# BNC_IO.net
KiCad netlist of a schematic drawn in Altium Designer
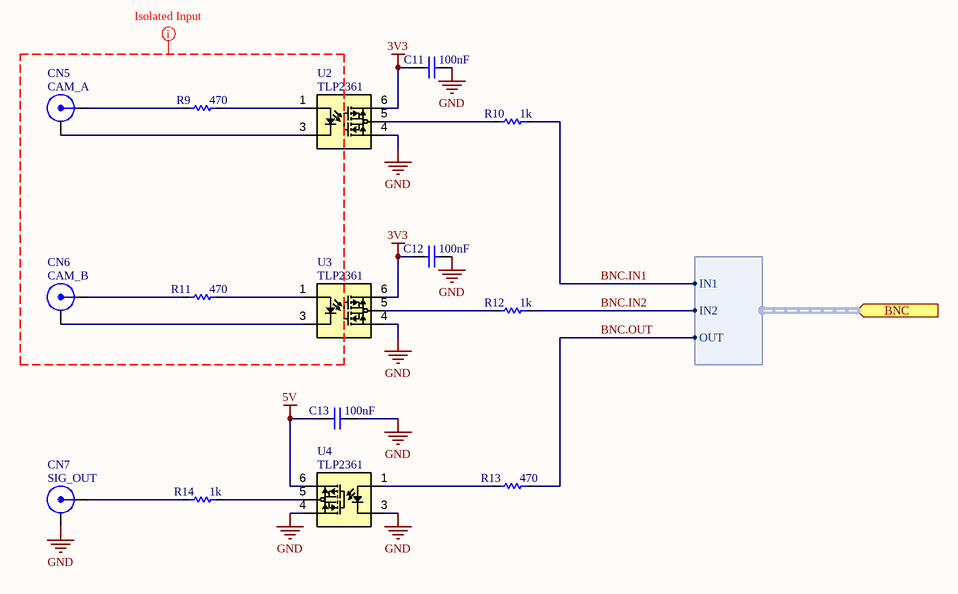
[diagram p0: BNC IO.SchDoc]

(export (version "E")
  (design (tool "Eeschema 10.0.6"))
  (components
    (comp (ref "C11")
      (value "100nF")
      (footprint "CAP_CHIP_0603")
      (description "0603 Multilayer Ceramic Capacitors MLCC")
      (fields (field (name "TOLERANCE") "10%") (field (name "PARTNUMBER") "CC0603KRX7R9BB104"))
      (libsource (lib "Sainsbury Wellcome Centre") (part "Cap"))
    )
    (comp (ref "C12")
      (value "100nF")
      (footprint "CAP_CHIP_0603")
      (description "0603 Multilayer Ceramic Capacitors MLCC")
      (fields (field (name "TOLERANCE") "10%") (field (name "PARTNUMBER") "CC0603KRX7R9BB104"))
      (libsource (lib "Sainsbury Wellcome Centre") (part "Cap"))
    )
    (comp (ref "C13")
      (value "100nF")
      (footprint "CAP_CHIP_0603")
      (description "0603 Multilayer Ceramic Capacitors MLCC")
      (fields (field (name "TOLERANCE") "10%") (field (name "PARTNUMBER") "CC0603KRX7R9BB104"))
      (libsource (lib "Sainsbury Wellcome Centre") (part "Cap"))
    )
    (comp (ref "CN5")
      (value "CAM_A")
      (footprint "BNC-MOLEX-731000105")
      (description "50 Ohms, BNC Right-Angle PCB Jack Receptacle, Nickel Plated Zinc Alloy Body, Low Profile")
      (fields (field (name "PARTNUMBER") "731000105"))
      (libsource (lib "Sainsbury Wellcome Centre") (part "RF-Jack"))
    )
    (comp (ref "CN6")
      (value "CAM_B")
      (footprint "BNC-MOLEX-731000105")
      (description "50 Ohms, BNC Right-Angle PCB Jack Receptacle, Nickel Plated Zinc Alloy Body, Low Profile")
      (fields (field (name "PARTNUMBER") "731000105"))
      (libsource (lib "Sainsbury Wellcome Centre") (part "RF-Jack"))
    )
    (comp (ref "CN7")
      (value "SIG_OUT")
      (footprint "BNC-MOLEX-731000105")
      (description "50 Ohms, BNC Right-Angle PCB Jack Receptacle, Nickel Plated Zinc Alloy Body, Low Profile")
      (fields (field (name "PARTNUMBER") "731000105"))
      (libsource (lib "Sainsbury Wellcome Centre") (part "RF-Jack"))
    )
    (comp (ref "R9")
      (value "470")
      (footprint "RES_CHIP_0603")
      (description "100mW Thick Film Resistors 75V ±100ppm/℃ ±1% 0603 Chip Resistor")
      (fields (field (name "PARTNUMBER") "0603WAF4700T5E") (field (name "TOLERANCE") "1%"))
      (libsource (lib "Sainsbury Wellcome Centre") (part "Res"))
    )
    (comp (ref "R10")
      (value "1k")
      (footprint "RES_CHIP_0603")
      (description "100mW Thick Film Resistors 75V ±100ppm/℃ ±1% 0603 Chip Resistor")
      (fields (field (name "PARTNUMBER") "0603WAF1001T5E") (field (name "TOLERANCE") "1%"))
      (libsource (lib "Sainsbury Wellcome Centre") (part "Res"))
    )
    (comp (ref "R11")
      (value "470")
      (footprint "RES_CHIP_0603")
      (description "100mW Thick Film Resistors 75V ±100ppm/℃ ±1% 0603 Chip Resistor")
      (fields (field (name "PARTNUMBER") "0603WAF4700T5E") (field (name "TOLERANCE") "1%"))
      (libsource (lib "Sainsbury Wellcome Centre") (part "Res"))
    )
    (comp (ref "R12")
      (value "1k")
      (footprint "RES_CHIP_0603")
      (description "100mW Thick Film Resistors 75V ±100ppm/℃ ±1% 0603 Chip Resistor")
      (fields (field (name "PARTNUMBER") "0603WAF1001T5E") (field (name "TOLERANCE") "1%"))
      (libsource (lib "Sainsbury Wellcome Centre") (part "Res"))
    )
    (comp (ref "R13")
      (value "470")
      (footprint "RES_CHIP_0603")
      (description "100mW Thick Film Resistors 75V ±100ppm/℃ ±1% 0603 Chip Resistor")
      (fields (field (name "PARTNUMBER") "0603WAF4700T5E") (field (name "TOLERANCE") "1%"))
      (libsource (lib "Sainsbury Wellcome Centre") (part "Res"))
    )
    (comp (ref "R14")
      (value "1k")
      (footprint "RES_CHIP_0603")
      (description "100mW Thick Film Resistors 75V ±100ppm/℃ ±1% 0603 Chip Resistor")
      (fields (field (name "PARTNUMBER") "0603WAF1001T5E") (field (name "TOLERANCE") "1%"))
      (libsource (lib "Sainsbury Wellcome Centre") (part "Res"))
    )
    (comp (ref "U2")
      (value "TLP2361")
      (footprint "SO5")
      (description "Logic IC Output Optocoupler, 1-Channel, 1-Element, 3750V Isolation, 20MBps")
      (fields (field (name "PARTNUMBER") "TLP2361(TPL,E(T"))
      (libsource (lib "Sainsbury Wellcome Centre") (part "Logic Output Optoisolator"))
    )
    (comp (ref "U3")
      (value "TLP2361")
      (footprint "SO5")
      (description "Logic IC Output Optocoupler, 1-Channel, 1-Element, 3750V Isolation, 20MBps")
      (fields (field (name "PARTNUMBER") "TLP2361(TPL,E(T"))
      (libsource (lib "Sainsbury Wellcome Centre") (part "Logic Output Optoisolator"))
    )
    (comp (ref "U4")
      (value "TLP2361")
      (footprint "SO5")
      (description "Logic IC Output Optocoupler, 1-Channel, 1-Element, 3750V Isolation, 20MBps")
      (fields (field (name "PARTNUMBER") "TLP2361(TPL,E(T"))
      (libsource (lib "") (part "Logic Output Optoisolator_1"))
    )
  )
  (nets
    (net (code "2") (name "/BNC.IN1") (class "Default")
      (node (ref "R10") (pin "2") (pinfunction "2_2") (pintype "passive"))
    )
    (net (code "3") (name "/BNC.IN2") (class "Default")
      (node (ref "R12") (pin "2") (pinfunction "2_2") (pintype "passive"))
    )
    (net (code "4") (name "/BNC.OUT") (class "Default")
      (node (ref "R13") (pin "2") (pinfunction "2_2") (pintype "passive"))
    )
    (net (code "6") (name "3V3") (class "Default")
      (node (ref "C11") (pin "2") (pinfunction "2_2") (pintype "passive"))
      (node (ref "C12") (pin "2") (pinfunction "2_2") (pintype "passive"))
      (node (ref "U2") (pin "6") (pinfunction "VCC_6") (pintype "passive"))
      (node (ref "U3") (pin "6") (pinfunction "VCC_6") (pintype "passive"))
    )
    (net (code "7") (name "5V") (class "Default")
      (node (ref "C13") (pin "2") (pinfunction "2_2") (pintype "passive"))
      (node (ref "U4") (pin "6") (pinfunction "VCC_6") (pintype "passive"))
    )
    (net (code "8") (name "GND") (class "Default")
      (node (ref "C11") (pin "1") (pinfunction "1_1") (pintype "passive"))
      (node (ref "C12") (pin "1") (pinfunction "1_1") (pintype "passive"))
      (node (ref "C13") (pin "1") (pinfunction "1_1") (pintype "passive"))
      (node (ref "CN7") (pin "2") (pinfunction "GND_2") (pintype "passive"))
      (node (ref "U2") (pin "4") (pinfunction "GND_4") (pintype "passive"))
      (node (ref "U3") (pin "4") (pinfunction "GND_4") (pintype "passive"))
      (node (ref "U4") (pin "3") (pinfunction "Cathode_3") (pintype "passive"))
      (node (ref "U4") (pin "4") (pinfunction "GND_4") (pintype "passive"))
    )
    (net (code "9") (name "Net-(CN5-GND)") (class "Default")
      (node (ref "CN5") (pin "2") (pinfunction "GND_2") (pintype "passive"))
      (node (ref "U2") (pin "3") (pinfunction "Cathode_3") (pintype "passive"))
    )
    (net (code "10") (name "Net-(CN5-SIG)") (class "Default")
      (node (ref "CN5") (pin "1") (pinfunction "SIG_1") (pintype "passive"))
      (node (ref "R9") (pin "1") (pinfunction "1_1") (pintype "passive"))
    )
    (net (code "11") (name "Net-(CN6-GND)") (class "Default")
      (node (ref "CN6") (pin "2") (pinfunction "GND_2") (pintype "passive"))
      (node (ref "U3") (pin "3") (pinfunction "Cathode_3") (pintype "passive"))
    )
    (net (code "12") (name "Net-(CN6-SIG)") (class "Default")
      (node (ref "CN6") (pin "1") (pinfunction "SIG_1") (pintype "passive"))
      (node (ref "R11") (pin "1") (pinfunction "1_1") (pintype "passive"))
    )
    (net (code "13") (name "Net-(CN7-SIG)") (class "Default")
      (node (ref "CN7") (pin "1") (pinfunction "SIG_1") (pintype "passive"))
      (node (ref "R14") (pin "1") (pinfunction "1_1") (pintype "passive"))
    )
    (net (code "14") (name "Net-(U2-Anode)") (class "Default")
      (node (ref "R9") (pin "2") (pinfunction "2_2") (pintype "passive"))
      (node (ref "U2") (pin "1") (pinfunction "Anode_1") (pintype "passive"))
    )
    (net (code "15") (name "Net-(U2-Vo)") (class "Default")
      (node (ref "R10") (pin "1") (pinfunction "1_1") (pintype "passive"))
      (node (ref "U2") (pin "5") (pinfunction "Vo_5") (pintype "passive"))
    )
    (net (code "16") (name "Net-(U3-Anode)") (class "Default")
      (node (ref "R11") (pin "2") (pinfunction "2_2") (pintype "passive"))
      (node (ref "U3") (pin "1") (pinfunction "Anode_1") (pintype "passive"))
    )
    (net (code "17") (name "Net-(U3-Vo)") (class "Default")
      (node (ref "R12") (pin "1") (pinfunction "1_1") (pintype "passive"))
      (node (ref "U3") (pin "5") (pinfunction "Vo_5") (pintype "passive"))
    )
    (net (code "18") (name "Net-(U4-Anode)") (class "Default")
      (node (ref "R13") (pin "1") (pinfunction "1_1") (pintype "passive"))
      (node (ref "U4") (pin "1") (pinfunction "Anode_1") (pintype "passive"))
    )
    (net (code "19") (name "Net-(U4-Vo)") (class "Default")
      (node (ref "R14") (pin "2") (pinfunction "2_2") (pintype "passive"))
      (node (ref "U4") (pin "5") (pinfunction "Vo_5") (pintype "passive"))
    )
  )
)
